# ProProject_Buck-Boost_1_2024-04-08.net
KiCad netlist of a schematic drawn in EasyEDA Pro
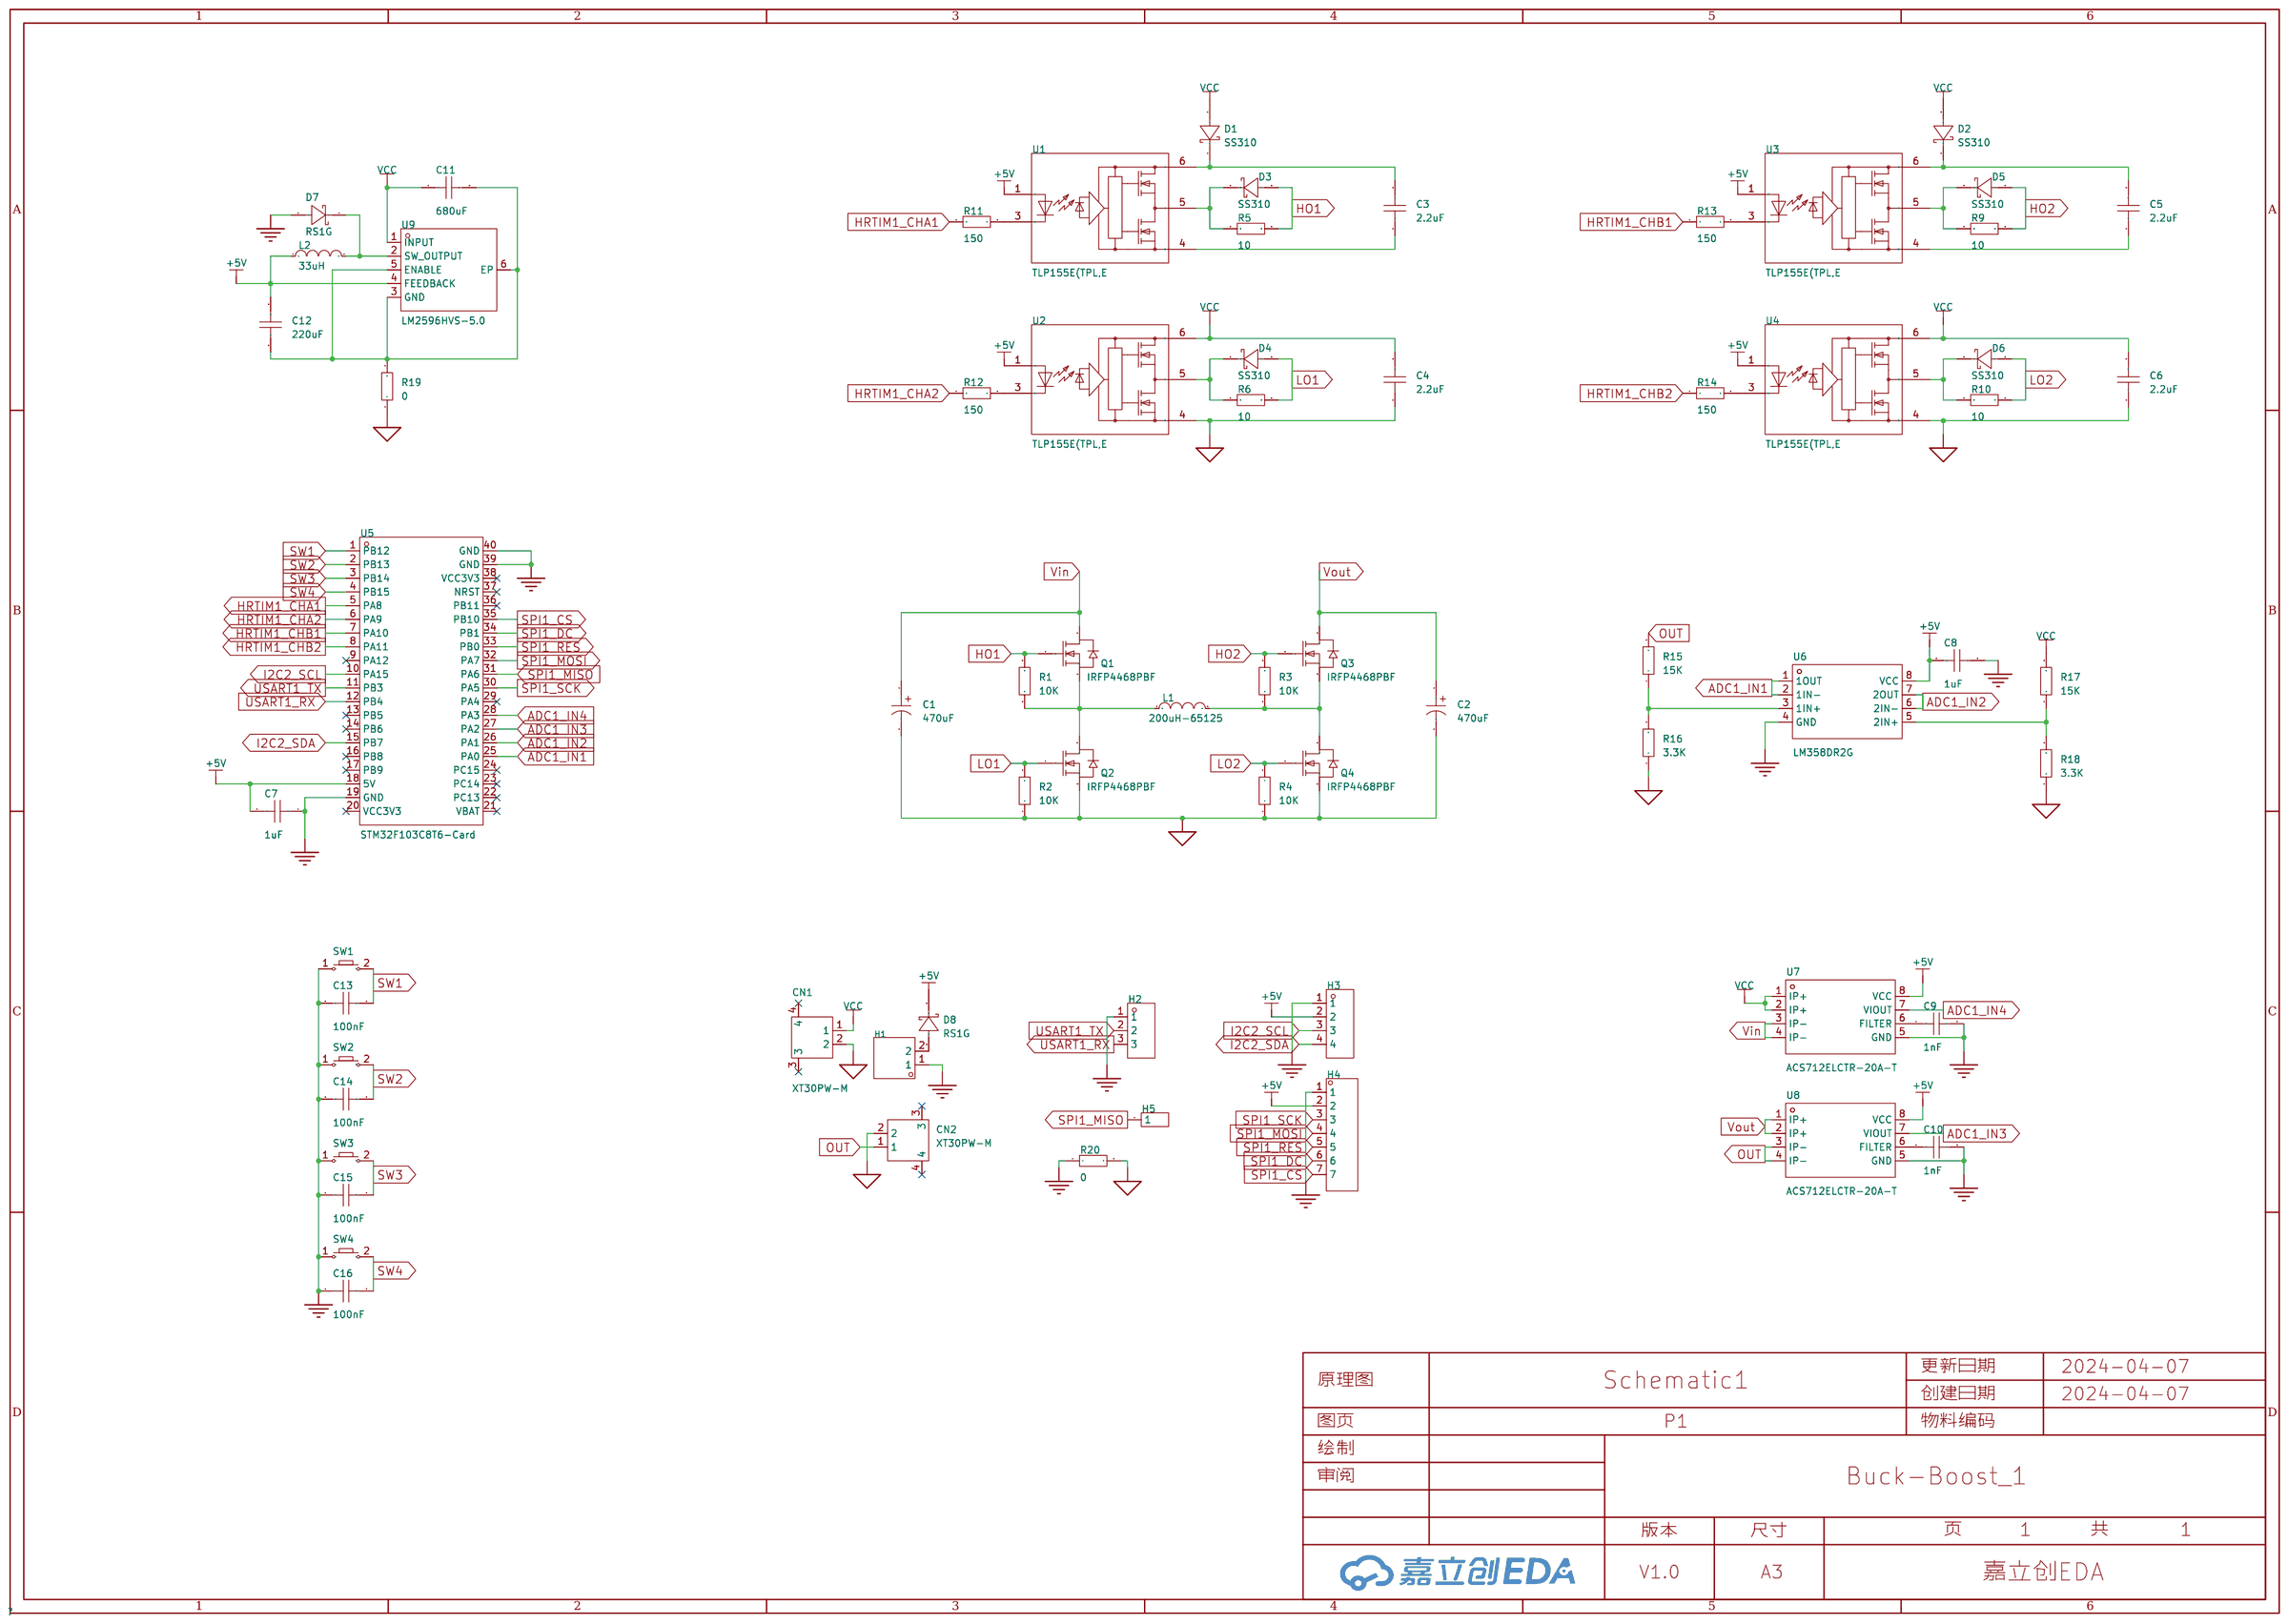
[diagram p0: schematic sheet]

(export (version "E")
  (design (tool "Eeschema 10.0.6"))
  (components
    (comp (ref "C1")
      (value "470uF")
      (footprint "easyedapro:CAP-TH_BD16.0-P7.50-D1.5-FD")
      (description "容值:470uF;精度:±20%;额定电压:120V;纹波电流:-;等效串联电阻:-;")
      (fields (field (name "Manufacturer Part") "ERS2BM471L35OT") (field (name "Manufacturer") "AISHI(艾华集团)"))
      (libsource (lib "easyedapro") (part "ERS2BM471L35OT"))
    )
    (comp (ref "C2")
      (value "470uF")
      (footprint "easyedapro:CAP-TH_BD16.0-P7.50-D1.5-FD")
      (description "容值:470uF;精度:±20%;额定电压:120V;纹波电流:-;等效串联电阻:-;")
      (fields (field (name "Manufacturer Part") "ERS2BM471L35OT") (field (name "Manufacturer") "AISHI(艾华集团)"))
      (libsource (lib "easyedapro") (part "ERS2BM471L35OT"))
    )
    (comp (ref "C3")
      (value "2.2uF")
      (footprint "easyedapro:C0603")
      (libsource (lib "easyedapro") (part "CapAcitance"))
    )
    (comp (ref "C4")
      (value "2.2uF")
      (footprint "easyedapro:C0603")
      (libsource (lib "easyedapro") (part "CapAcitance"))
    )
    (comp (ref "C5")
      (value "2.2uF")
      (footprint "easyedapro:C0603")
      (libsource (lib "easyedapro") (part "CapAcitance"))
    )
    (comp (ref "C6")
      (value "2.2uF")
      (footprint "easyedapro:C0603")
      (libsource (lib "easyedapro") (part "CapAcitance"))
    )
    (comp (ref "C7")
      (value "1uF")
      (footprint "easyedapro:C0603")
      (libsource (lib "easyedapro") (part "CapAcitance"))
    )
    (comp (ref "C8")
      (value "1uF")
      (footprint "easyedapro:C0603")
      (libsource (lib "easyedapro") (part "CapAcitance"))
    )
    (comp (ref "C9")
      (value "1nF")
      (footprint "easyedapro:C0603")
      (libsource (lib "easyedapro") (part "CapAcitance"))
    )
    (comp (ref "C10")
      (value "1nF")
      (footprint "easyedapro:C0603")
      (libsource (lib "easyedapro") (part "CapAcitance"))
    )
    (comp (ref "C11")
      (value "680uF")
      (footprint "easyedapro:C0603")
      (libsource (lib "easyedapro") (part "CapAcitance"))
    )
    (comp (ref "C12")
      (value "220uF")
      (footprint "easyedapro:C0603")
      (libsource (lib "easyedapro") (part "CapAcitance"))
    )
    (comp (ref "C13")
      (value "100nF")
      (footprint "easyedapro:C0603")
      (libsource (lib "easyedapro") (part "CapAcitance"))
    )
    (comp (ref "C14")
      (value "100nF")
      (footprint "easyedapro:C0603")
      (libsource (lib "easyedapro") (part "CapAcitance"))
    )
    (comp (ref "C15")
      (value "100nF")
      (footprint "easyedapro:C0603")
      (libsource (lib "easyedapro") (part "CapAcitance"))
    )
    (comp (ref "C16")
      (value "100nF")
      (footprint "easyedapro:C0603")
      (libsource (lib "easyedapro") (part "CapAcitance"))
    )
    (comp (ref "CN1")
      (value "XT30PW-M")
      (footprint "easyedapro:CONN-TH_XT30PW-M")
      (description "类别:-;类型1:-;")
      (fields (field (name "Manufacturer") "AMASS(艾迈斯)"))
      (libsource (lib "easyedapro") (part "XT30PW-M"))
    )
    (comp (ref "CN2")
      (value "XT30PW-M")
      (footprint "easyedapro:CONN-TH_XT30PW-M")
      (description "类别:-;类型1:-;")
      (fields (field (name "Manufacturer") "AMASS(艾迈斯)"))
      (libsource (lib "easyedapro") (part "XT30PW-M"))
    )
    (comp (ref "D1")
      (value "SS310")
      (footprint "easyedapro:SMC_L6.9-W5.9-LS7.9-RD")
      (fields (field (name "Manufacturer") "MDD"))
      (libsource (lib "easyedapro") (part "SS56_C5161914"))
    )
    (comp (ref "D2")
      (value "SS310")
      (footprint "easyedapro:SMC_L6.9-W5.9-LS7.9-RD")
      (fields (field (name "Manufacturer") "MDD"))
      (libsource (lib "easyedapro") (part "SS56_C5161914"))
    )
    (comp (ref "D3")
      (value "SS310")
      (footprint "easyedapro:SMC_L6.9-W5.9-LS7.9-RD")
      (fields (field (name "Manufacturer") "MDD"))
      (libsource (lib "easyedapro") (part "SS56_C5161914"))
    )
    (comp (ref "D4")
      (value "SS310")
      (footprint "easyedapro:SMC_L6.9-W5.9-LS7.9-RD")
      (fields (field (name "Manufacturer") "MDD"))
      (libsource (lib "easyedapro") (part "SS56_C5161914"))
    )
    (comp (ref "D5")
      (value "SS310")
      (footprint "easyedapro:SMC_L6.9-W5.9-LS7.9-RD")
      (fields (field (name "Manufacturer") "MDD"))
      (libsource (lib "easyedapro") (part "SS56_C5161914"))
    )
    (comp (ref "D6")
      (value "SS310")
      (footprint "easyedapro:SMC_L6.9-W5.9-LS7.9-RD")
      (fields (field (name "Manufacturer") "MDD"))
      (libsource (lib "easyedapro") (part "SS56_C5161914"))
    )
    (comp (ref "D7")
      (value "RS1G")
      (footprint "easyedapro:SMC_L6.9-W5.9-LS7.9-RD")
      (fields (field (name "Manufacturer") "宏迦橙"))
      (libsource (lib "easyedapro") (part "SS56_C5161914"))
    )
    (comp (ref "D8")
      (value "RS1G")
      (footprint "easyedapro:SMC_L6.9-W5.9-LS7.9-RD")
      (fields (field (name "Manufacturer") "宏迦橙"))
      (libsource (lib "easyedapro") (part "SS56_C5161914"))
    )
    (comp (ref "H1")
      (value "~")
      (footprint "easyedapro:HDR-TH_2P-P2.54-V-M-1")
      (libsource (lib "easyedapro") (part "210S-1*2P L=11.6MMGold-plated black"))
    )
    (comp (ref "H2")
      (value "~")
      (footprint "easyedapro:HDR-TH_3P-P2.54-V-M")
      (libsource (lib "easyedapro") (part "PZ254V-11-03P_C2937625"))
    )
    (comp (ref "H3")
      (value "~")
      (footprint "easyedapro:HDR-TH_4P-P2.54-V-F")
      (libsource (lib "easyedapro") (part "2.54-1*4P母"))
    )
    (comp (ref "H4")
      (value "~")
      (footprint "easyedapro:HDR-TH_7P-P2.54-V-F")
      (libsource (lib "easyedapro") (part "220S-1*7P H=8.5MM Ytype Gold-plated"))
    )
    (comp (ref "H5")
      (value "~")
      (footprint "easyedapro:HDR-TH_1P-V-M_XKB_X4611WV-01I-C28D40")
      (libsource (lib "easyedapro") (part "HDR_1x1"))
    )
    (comp (ref "L1")
      (value "200uH-65125")
      (footprint "easyedapro:IND-TH_200UH-65125")
      (libsource (lib "easyedapro") (part "200UH-65125"))
    )
    (comp (ref "L2")
      (value "33uH")
      (footprint "easyedapro:L0603")
      (fields
        (field (name "Manufacturer Part") "MGV0603330M-10")
        (field (name "Manufacturer") "Laird-Signal Integrity Products")
      )
      (libsource (lib "easyedapro") (part "SDFL1608S100KTF"))
    )
    (comp (ref "Q1")
      (value "IRFP4468PBF")
      (footprint "easyedapro:TO-247AC-3_L15.8-W5.0-P5.46-L")
      (fields (field (name "Manufacturer") "Infineon(英飞凌)"))
      (libsource (lib "easyedapro") (part "IRFP4468PBF"))
    )
    (comp (ref "Q2")
      (value "IRFP4468PBF")
      (footprint "easyedapro:TO-247AC-3_L15.8-W5.0-P5.46-L")
      (fields (field (name "Manufacturer") "Infineon(英飞凌)"))
      (libsource (lib "easyedapro") (part "IRFP4468PBF"))
    )
    (comp (ref "Q3")
      (value "IRFP4468PBF")
      (footprint "easyedapro:TO-247AC-3_L15.8-W5.0-P5.46-L")
      (fields (field (name "Manufacturer") "Infineon(英飞凌)"))
      (libsource (lib "easyedapro") (part "IRFP4468PBF"))
    )
    (comp (ref "Q4")
      (value "IRFP4468PBF")
      (footprint "easyedapro:TO-247AC-3_L15.8-W5.0-P5.46-L")
      (fields (field (name "Manufacturer") "Infineon(英飞凌)"))
      (libsource (lib "easyedapro") (part "IRFP4468PBF"))
    )
    (comp (ref "R1") (value "10K") (footprint "easyedapro:R0603") (libsource (lib "easyedapro") (part "电阻")))
    (comp (ref "R2") (value "10K") (footprint "easyedapro:R0603") (libsource (lib "easyedapro") (part "电阻")))
    (comp (ref "R3") (value "10K") (footprint "easyedapro:R0603") (libsource (lib "easyedapro") (part "电阻")))
    (comp (ref "R4") (value "10K") (footprint "easyedapro:R0603") (libsource (lib "easyedapro") (part "电阻")))
    (comp (ref "R5") (value "10") (footprint "easyedapro:R0603") (libsource (lib "easyedapro") (part "电阻")))
    (comp (ref "R6") (value "10") (footprint "easyedapro:R0603") (libsource (lib "easyedapro") (part "电阻")))
    (comp (ref "R9") (value "10") (footprint "easyedapro:R0603") (libsource (lib "easyedapro") (part "电阻")))
    (comp (ref "R10") (value "10") (footprint "easyedapro:R0603") (libsource (lib "easyedapro") (part "电阻")))
    (comp (ref "R11") (value "150") (footprint "easyedapro:R0603") (libsource (lib "easyedapro") (part "电阻")))
    (comp (ref "R12") (value "150") (footprint "easyedapro:R0603") (libsource (lib "easyedapro") (part "电阻")))
    (comp (ref "R13") (value "150") (footprint "easyedapro:R0603") (libsource (lib "easyedapro") (part "电阻")))
    (comp (ref "R14") (value "150") (footprint "easyedapro:R0603") (libsource (lib "easyedapro") (part "电阻")))
    (comp (ref "R15") (value "15K") (footprint "easyedapro:R0603") (libsource (lib "easyedapro") (part "电阻")))
    (comp (ref "R16")
      (value "3.3K")
      (footprint "easyedapro:R0603")
      (libsource (lib "easyedapro") (part "电阻"))
    )
    (comp (ref "R17") (value "15K") (footprint "easyedapro:R0603") (libsource (lib "easyedapro") (part "电阻")))
    (comp (ref "R18")
      (value "3.3K")
      (footprint "easyedapro:R0603")
      (libsource (lib "easyedapro") (part "电阻"))
    )
    (comp (ref "R19") (value "0") (footprint "easyedapro:R0603") (libsource (lib "easyedapro") (part "电阻")))
    (comp (ref "R20") (value "0") (footprint "easyedapro:R0603") (libsource (lib "easyedapro") (part "电阻")))
    (comp (ref "SW1")
      (value "~")
      (footprint "easyedapro:Key_SMD_3x4x2")
      (libsource (lib "easyedapro") (part "轻触按键x2"))
    )
    (comp (ref "SW2")
      (value "~")
      (footprint "easyedapro:Key_SMD_3x4x2")
      (libsource (lib "easyedapro") (part "轻触按键x2"))
    )
    (comp (ref "SW3")
      (value "~")
      (footprint "easyedapro:Key_SMD_3x4x2")
      (libsource (lib "easyedapro") (part "轻触按键x2"))
    )
    (comp (ref "SW4")
      (value "~")
      (footprint "easyedapro:Key_SMD_3x4x2")
      (libsource (lib "easyedapro") (part "轻触按键x2"))
    )
    (comp (ref "U1")
      (value "TLP155E(TPL,E")
      (footprint "easyedapro:OPTO-SMD-5_L3.7-W4.6-P1.27-LS7.0-BR")
      (description "输入类型:DC;电源电压:10V~30V;共模瞬变抗扰度CMTI:15kV/us;传播延迟tpLH/tpHL:170ns；170ns;")
      (fields (field (name "Manufacturer") "TOSHIBA(东芝)"))
      (libsource (lib "easyedapro") (part "TLP155E(TPL,E"))
    )
    (comp (ref "U2")
      (value "TLP155E(TPL,E")
      (footprint "easyedapro:OPTO-SMD-5_L3.7-W4.6-P1.27-LS7.0-BR")
      (description "输入类型:DC;电源电压:10V~30V;共模瞬变抗扰度CMTI:15kV/us;传播延迟tpLH/tpHL:170ns；170ns;")
      (fields (field (name "Manufacturer") "TOSHIBA(东芝)"))
      (libsource (lib "easyedapro") (part "TLP155E(TPL,E"))
    )
    (comp (ref "U3")
      (value "TLP155E(TPL,E")
      (footprint "easyedapro:OPTO-SMD-5_L3.7-W4.6-P1.27-LS7.0-BR")
      (description "输入类型:DC;电源电压:10V~30V;共模瞬变抗扰度CMTI:15kV/us;传播延迟tpLH/tpHL:170ns；170ns;")
      (fields (field (name "Manufacturer") "TOSHIBA(东芝)"))
      (libsource (lib "easyedapro") (part "TLP155E(TPL,E"))
    )
    (comp (ref "U4")
      (value "TLP155E(TPL,E")
      (footprint "easyedapro:OPTO-SMD-5_L3.7-W4.6-P1.27-LS7.0-BR")
      (description "输入类型:DC;电源电压:10V~30V;共模瞬变抗扰度CMTI:15kV/us;传播延迟tpLH/tpHL:170ns；170ns;")
      (fields (field (name "Manufacturer") "TOSHIBA(东芝)"))
      (libsource (lib "easyedapro") (part "TLP155E(TPL,E"))
    )
    (comp (ref "U5")
      (value "STM32F103C8T6-Card")
      (footprint "easyedapro:CONN-TH_L53.3-W22.9_STM32F103C8T6-CARD")
      (libsource (lib "easyedapro") (part "STM32F103C8T6-CARD"))
    )
    (comp (ref "U6")
      (value "LM358DR2G")
      (footprint "easyedapro:SOIC-8_L5.0-W4.0-P1.27-LS6.0-BL")
      (description "放大器数:双路;增益带宽积(GBP):1MHz;输入偏置电流(Ib):45nA;压摆率(SR):-;带宽(-3db):-;")
      (fields (field (name "Manufacturer") "onsemi(安森美)"))
      (libsource (lib "easyedapro") (part "LM358DR2G"))
    )
    (comp (ref "U7")
      (value "ACS712ELCTR-20A-T")
      (footprint "easyedapro:SOIC-8_L4.9-W3.9-P1.27-LS6.0-BL")
      (description "电流测量范围:20A;灵敏度:100mV/A;")
      (fields (field (name "Manufacturer") "ALLEGRO(美国埃戈罗)"))
      (libsource (lib "easyedapro") (part "ACS712ELCTR-20A-T"))
    )
    (comp (ref "U8")
      (value "ACS712ELCTR-20A-T")
      (footprint "easyedapro:SOIC-8_L4.9-W3.9-P1.27-LS6.0-BL")
      (description "电流测量范围:20A;灵敏度:100mV/A;")
      (fields (field (name "Manufacturer") "ALLEGRO(美国埃戈罗)"))
      (libsource (lib "easyedapro") (part "ACS712ELCTR-20A-T"))
    )
    (comp (ref "U9")
      (value "LM2596HVS-5.0")
      (footprint "easyedapro:TO-263-5_L10.0-W9.0-P1.70-LS15.0-BL")
      (fields (field (name "Manufacturer") "TECH PUBLIC(台舟)"))
      (libsource (lib "easyedapro") (part "LM2596HVS-5.0_C18197847"))
    )
  )
  (nets
    (net (code "1") (name "+5V") (class "Default")
      (node (ref "C12") (pin "2") (pinfunction "2_2") (pintype "input"))
      (node (ref "C7") (pin "2") (pinfunction "2_2") (pintype "input"))
      (node (ref "C8") (pin "1") (pinfunction "1_1") (pintype "input"))
      (node (ref "D8") (pin "1") (pinfunction "K_1") (pintype "unspecified"))
      (node (ref "H3") (pin "2") (pinfunction "2_2") (pintype "unspecified"))
      (node (ref "H4") (pin "2") (pinfunction "2_2") (pintype "unspecified"))
      (node (ref "L2") (pin "1") (pinfunction "1_1") (pintype "unspecified"))
      (node (ref "U1") (pin "1") (pinfunction "AN_1") (pintype "unspecified"))
      (node (ref "U2") (pin "1") (pinfunction "AN_1") (pintype "unspecified"))
      (node (ref "U3") (pin "1") (pinfunction "AN_1") (pintype "unspecified"))
      (node (ref "U4") (pin "1") (pinfunction "AN_1") (pintype "unspecified"))
      (node (ref "U5") (pin "18") (pinfunction "5V_18") (pintype "unspecified"))
      (node (ref "U6") (pin "8") (pinfunction "VCC_8") (pintype "unspecified"))
      (node (ref "U7") (pin "8") (pinfunction "VCC_8") (pintype "unspecified"))
      (node (ref "U8") (pin "8") (pinfunction "VCC_8") (pintype "unspecified"))
      (node (ref "U9") (pin "4") (pinfunction "FEEDBACK_4") (pintype "unspecified"))
    )
    (net (code "2") (name "ADC1_IN1") (class "Default")
      (node (ref "U5") (pin "25") (pinfunction "PA0_25") (pintype "unspecified"))
      (node (ref "U6") (pin "1") (pinfunction "1OUT_1") (pintype "unspecified"))
      (node (ref "U6") (pin "2") (pinfunction "1IN-_2") (pintype "unspecified"))
    )
    (net (code "3") (name "ADC1_IN2") (class "Default")
      (node (ref "U5") (pin "26") (pinfunction "PA1_26") (pintype "unspecified"))
      (node (ref "U6") (pin "6") (pinfunction "2IN-_6") (pintype "unspecified"))
      (node (ref "U6") (pin "7") (pinfunction "2OUT_7") (pintype "unspecified"))
    )
    (net (code "4") (name "ADC1_IN3") (class "Default")
      (node (ref "U5") (pin "27") (pinfunction "PA2_27") (pintype "unspecified"))
      (node (ref "U8") (pin "7") (pinfunction "VIOUT_7") (pintype "unspecified"))
    )
    (net (code "5") (name "ADC1_IN4") (class "Default")
      (node (ref "U5") (pin "28") (pinfunction "PA3_28") (pintype "unspecified"))
      (node (ref "U7") (pin "7") (pinfunction "VIOUT_7") (pintype "unspecified"))
    )
    (net (code "6") (name "AGND") (class "Default")
      (node (ref "C1") (pin "2") (pinfunction "2_2") (pintype "input"))
      (node (ref "C2") (pin "2") (pinfunction "2_2") (pintype "input"))
      (node (ref "C4") (pin "1") (pinfunction "1_1") (pintype "input"))
      (node (ref "C6") (pin "1") (pinfunction "1_1") (pintype "input"))
      (node (ref "CN1") (pin "2") (pinfunction "2_2") (pintype "unspecified"))
      (node (ref "CN2") (pin "2") (pinfunction "2_2") (pintype "unspecified"))
      (node (ref "Q2") (pin "3") (pinfunction "S_3") (pintype "unspecified"))
      (node (ref "Q4") (pin "3") (pinfunction "S_3") (pintype "unspecified"))
      (node (ref "R16") (pin "1") (pinfunction "1_1") (pintype "input"))
      (node (ref "R18") (pin "1") (pinfunction "1_1") (pintype "input"))
      (node (ref "R19") (pin "1") (pinfunction "1_1") (pintype "input"))
      (node (ref "R2") (pin "1") (pinfunction "1_1") (pintype "input"))
      (node (ref "R20") (pin "2") (pinfunction "2_2") (pintype "input"))
      (node (ref "R4") (pin "1") (pinfunction "1_1") (pintype "input"))
      (node (ref "U2") (pin "4") (pinfunction "GND_4") (pintype "unspecified"))
      (node (ref "U4") (pin "4") (pinfunction "GND_4") (pintype "unspecified"))
    )
    (net (code "7") (name "GND") (class "Default")
      (node (ref "C10") (pin "2") (pinfunction "2_2") (pintype "input"))
      (node (ref "C13") (pin "1") (pinfunction "1_1") (pintype "input"))
      (node (ref "C14") (pin "1") (pinfunction "1_1") (pintype "input"))
      (node (ref "C15") (pin "1") (pinfunction "1_1") (pintype "input"))
      (node (ref "C16") (pin "1") (pinfunction "1_1") (pintype "input"))
      (node (ref "C7") (pin "1") (pinfunction "1_1") (pintype "input"))
      (node (ref "C8") (pin "2") (pinfunction "2_2") (pintype "input"))
      (node (ref "C9") (pin "2") (pinfunction "2_2") (pintype "input"))
      (node (ref "D7") (pin "2") (pinfunction "A_2") (pintype "unspecified"))
      (node (ref "H1") (pin "1") (pinfunction "1_1") (pintype "input"))
      (node (ref "H2") (pin "1") (pinfunction "1_1") (pintype "input"))
      (node (ref "H3") (pin "1") (pinfunction "1_1") (pintype "unspecified"))
      (node (ref "H4") (pin "1") (pinfunction "1_1") (pintype "unspecified"))
      (node (ref "R20") (pin "1") (pinfunction "1_1") (pintype "input"))
      (node (ref "SW1") (pin "1") (pinfunction "1_1") (pintype "input"))
      (node (ref "SW2") (pin "1") (pinfunction "1_1") (pintype "input"))
      (node (ref "SW3") (pin "1") (pinfunction "1_1") (pintype "input"))
      (node (ref "SW4") (pin "1") (pinfunction "1_1") (pintype "input"))
      (node (ref "U5") (pin "19") (pinfunction "GND_19") (pintype "unspecified"))
      (node (ref "U5") (pin "39") (pinfunction "GND_39") (pintype "unspecified"))
      (node (ref "U5") (pin "40") (pinfunction "GND_40") (pintype "unspecified"))
      (node (ref "U6") (pin "4") (pinfunction "GND_4") (pintype "unspecified"))
      (node (ref "U7") (pin "5") (pinfunction "GND_5") (pintype "unspecified"))
      (node (ref "U8") (pin "5") (pinfunction "GND_5") (pintype "unspecified"))
    )
    (net (code "8") (name "HO1") (class "Default")
      (node (ref "D3") (pin "2") (pinfunction "A_2") (pintype "unspecified"))
      (node (ref "Q1") (pin "1") (pinfunction "G_1") (pintype "unspecified"))
      (node (ref "R1") (pin "2") (pinfunction "2_2") (pintype "input"))
      (node (ref "R5") (pin "2") (pinfunction "2_2") (pintype "input"))
    )
    (net (code "9") (name "HO2") (class "Default")
      (node (ref "D5") (pin "2") (pinfunction "A_2") (pintype "unspecified"))
      (node (ref "Q3") (pin "1") (pinfunction "G_1") (pintype "unspecified"))
      (node (ref "R3") (pin "2") (pinfunction "2_2") (pintype "input"))
      (node (ref "R9") (pin "2") (pinfunction "2_2") (pintype "input"))
    )
    (net (code "10") (name "HRTIM1_CHA1") (class "Default")
      (node (ref "R11") (pin "1") (pinfunction "1_1") (pintype "input"))
      (node (ref "U5") (pin "5") (pinfunction "PA8_5") (pintype "unspecified"))
    )
    (net (code "11") (name "HRTIM1_CHA2") (class "Default")
      (node (ref "R12") (pin "1") (pinfunction "1_1") (pintype "input"))
      (node (ref "U5") (pin "6") (pinfunction "PA9_6") (pintype "unspecified"))
    )
    (net (code "12") (name "HRTIM1_CHB1") (class "Default")
      (node (ref "R13") (pin "1") (pinfunction "1_1") (pintype "input"))
      (node (ref "U5") (pin "7") (pinfunction "PA10_7") (pintype "unspecified"))
    )
    (net (code "13") (name "HRTIM1_CHB2") (class "Default")
      (node (ref "R14") (pin "1") (pinfunction "1_1") (pintype "input"))
      (node (ref "U5") (pin "8") (pinfunction "PA11_8") (pintype "unspecified"))
    )
    (net (code "14") (name "I2C2_SCL") (class "Default")
      (node (ref "H3") (pin "3") (pinfunction "3_3") (pintype "unspecified"))
      (node (ref "U5") (pin "10") (pinfunction "PA15_10") (pintype "unspecified"))
    )
    (net (code "15") (name "I2C2_SDA") (class "Default")
      (node (ref "H3") (pin "4") (pinfunction "4_4") (pintype "unspecified"))
      (node (ref "U5") (pin "15") (pinfunction "PB7_15") (pintype "unspecified"))
    )
    (net (code "16") (name "LO1") (class "Default")
      (node (ref "D4") (pin "2") (pinfunction "A_2") (pintype "unspecified"))
      (node (ref "Q2") (pin "1") (pinfunction "G_1") (pintype "unspecified"))
      (node (ref "R2") (pin "2") (pinfunction "2_2") (pintype "input"))
      (node (ref "R6") (pin "2") (pinfunction "2_2") (pintype "input"))
    )
    (net (code "17") (name "LO2") (class "Default")
      (node (ref "D6") (pin "2") (pinfunction "A_2") (pintype "unspecified"))
      (node (ref "Q4") (pin "1") (pinfunction "G_1") (pintype "unspecified"))
      (node (ref "R10") (pin "2") (pinfunction "2_2") (pintype "input"))
      (node (ref "R4") (pin "2") (pinfunction "2_2") (pintype "input"))
    )
    (net (code "18") (name "Net-(D1-K)") (class "Default")
      (node (ref "C3") (pin "2") (pinfunction "2_2") (pintype "input"))
      (node (ref "D1") (pin "1") (pinfunction "K_1") (pintype "unspecified"))
      (node (ref "U1") (pin "6") (pinfunction "VCC_6") (pintype "unspecified"))
    )
    (net (code "19") (name "Net-(D2-K)") (class "Default")
      (node (ref "C5") (pin "2") (pinfunction "2_2") (pintype "input"))
      (node (ref "D2") (pin "1") (pinfunction "K_1") (pintype "unspecified"))
      (node (ref "U3") (pin "6") (pinfunction "VCC_6") (pintype "unspecified"))
    )
    (net (code "20") (name "Net-(D3-K)") (class "Default")
      (node (ref "D3") (pin "1") (pinfunction "K_1") (pintype "unspecified"))
      (node (ref "R5") (pin "1") (pinfunction "1_1") (pintype "input"))
      (node (ref "U1") (pin "5") (pinfunction "VO_5") (pintype "unspecified"))
    )
    (net (code "21") (name "Net-(D4-K)") (class "Default")
      (node (ref "D4") (pin "1") (pinfunction "K_1") (pintype "unspecified"))
      (node (ref "R6") (pin "1") (pinfunction "1_1") (pintype "input"))
      (node (ref "U2") (pin "5") (pinfunction "VO_5") (pintype "unspecified"))
    )
    (net (code "22") (name "Net-(D5-K)") (class "Default")
      (node (ref "D5") (pin "1") (pinfunction "K_1") (pintype "unspecified"))
      (node (ref "R9") (pin "1") (pinfunction "1_1") (pintype "input"))
      (node (ref "U3") (pin "5") (pinfunction "VO_5") (pintype "unspecified"))
    )
    (net (code "23") (name "Net-(D6-K)") (class "Default")
      (node (ref "D6") (pin "1") (pinfunction "K_1") (pintype "unspecified"))
      (node (ref "R10") (pin "1") (pinfunction "1_1") (pintype "input"))
      (node (ref "U4") (pin "5") (pinfunction "VO_5") (pintype "unspecified"))
    )
    (net (code "24") (name "Net-(D7-K)") (class "Default")
      (node (ref "D7") (pin "1") (pinfunction "K_1") (pintype "unspecified"))
      (node (ref "L2") (pin "2") (pinfunction "2_2") (pintype "unspecified"))
      (node (ref "U9") (pin "2") (pinfunction "SW_OUTPUT_2") (pintype "unspecified"))
    )
    (net (code "25") (name "Net-(D8-A)") (class "Default")
      (node (ref "D8") (pin "2") (pinfunction "A_2") (pintype "unspecified"))
      (node (ref "H1") (pin "2") (pinfunction "2_2") (pintype "input"))
    )
    (net (code "26") (name "Net-(Q1-S)") (class "Default")
      (node (ref "L1") (pin "1") (pinfunction "1_1") (pintype "input"))
      (node (ref "Q1") (pin "3") (pinfunction "S_3") (pintype "unspecified"))
      (node (ref "Q2") (pin "2") (pinfunction "D_2") (pintype "unspecified"))
      (node (ref "R1") (pin "1") (pinfunction "1_1") (pintype "input"))
    )
    (net (code "27") (name "Net-(Q3-S)") (class "Default")
      (node (ref "L1") (pin "2") (pinfunction "2_2") (pintype "input"))
      (node (ref "Q3") (pin "3") (pinfunction "S_3") (pintype "unspecified"))
      (node (ref "Q4") (pin "2") (pinfunction "D_2") (pintype "unspecified"))
      (node (ref "R3") (pin "1") (pinfunction "1_1") (pintype "input"))
    )
    (net (code "28") (name "Net-(U1-CAT)") (class "Default")
      (node (ref "R11") (pin "2") (pinfunction "2_2") (pintype "input"))
      (node (ref "U1") (pin "3") (pinfunction "CAT_3") (pintype "unspecified"))
    )
    (net (code "29") (name "Net-(U1-GND)") (class "Default")
      (node (ref "C3") (pin "1") (pinfunction "1_1") (pintype "input"))
      (node (ref "U1") (pin "4") (pinfunction "GND_4") (pintype "unspecified"))
    )
    (net (code "30") (name "Net-(U2-CAT)") (class "Default")
      (node (ref "R12") (pin "2") (pinfunction "2_2") (pintype "input"))
      (node (ref "U2") (pin "3") (pinfunction "CAT_3") (pintype "unspecified"))
    )
    (net (code "31") (name "Net-(U3-CAT)") (class "Default")
      (node (ref "R13") (pin "2") (pinfunction "2_2") (pintype "input"))
      (node (ref "U3") (pin "3") (pinfunction "CAT_3") (pintype "unspecified"))
    )
    (net (code "32") (name "Net-(U3-GND)") (class "Default")
      (node (ref "C5") (pin "1") (pinfunction "1_1") (pintype "input"))
      (node (ref "U3") (pin "4") (pinfunction "GND_4") (pintype "unspecified"))
    )
    (net (code "33") (name "Net-(U4-CAT)") (class "Default")
      (node (ref "R14") (pin "2") (pinfunction "2_2") (pintype "input"))
      (node (ref "U4") (pin "3") (pinfunction "CAT_3") (pintype "unspecified"))
    )
    (net (code "34") (name "Net-(U6-1IN+)") (class "Default")
      (node (ref "R15") (pin "1") (pinfunction "1_1") (pintype "input"))
      (node (ref "R16") (pin "2") (pinfunction "2_2") (pintype "input"))
      (node (ref "U6") (pin "3") (pinfunction "1IN+_3") (pintype "unspecified"))
    )
    (net (code "35") (name "Net-(U6-2IN+)") (class "Default")
      (node (ref "R17") (pin "1") (pinfunction "1_1") (pintype "input"))
      (node (ref "R18") (pin "2") (pinfunction "2_2") (pintype "input"))
      (node (ref "U6") (pin "5") (pinfunction "2IN+_5") (pintype "unspecified"))
    )
    (net (code "36") (name "Net-(U7-FILTER)") (class "Default")
      (node (ref "C9") (pin "1") (pinfunction "1_1") (pintype "input"))
      (node (ref "U7") (pin "6") (pinfunction "FILTER_6") (pintype "unspecified"))
    )
    (net (code "37") (name "Net-(U8-FILTER)") (class "Default")
      (node (ref "C10") (pin "1") (pinfunction "1_1") (pintype "input"))
      (node (ref "U8") (pin "6") (pinfunction "FILTER_6") (pintype "unspecified"))
    )
    (net (code "38") (name "Net-(U9-ENABLE)") (class "Default")
      (node (ref "C11") (pin "2") (pinfunction "2_2") (pintype "input"))
      (node (ref "C12") (pin "1") (pinfunction "1_1") (pintype "input"))
      (node (ref "R19") (pin "2") (pinfunction "2_2") (pintype "input"))
      (node (ref "U9") (pin "3") (pinfunction "GND_3") (pintype "unspecified"))
      (node (ref "U9") (pin "5") (pinfunction "ENABLE_5") (pintype "unspecified"))
      (node (ref "U9") (pin "6") (pinfunction "EP_6") (pintype "unspecified"))
    )
    (net (code "39") (name "OUT") (class "Default")
      (node (ref "CN2") (pin "1") (pinfunction "1_1") (pintype "unspecified"))
      (node (ref "R15") (pin "2") (pinfunction "2_2") (pintype "input"))
      (node (ref "U8") (pin "3") (pinfunction "IP-_3") (pintype "unspecified"))
      (node (ref "U8") (pin "4") (pinfunction "IP-_4") (pintype "unspecified"))
    )
    (net (code "40") (name "SPI1_CS") (class "Default")
      (node (ref "H4") (pin "7") (pinfunction "7_7") (pintype "unspecified"))
      (node (ref "U5") (pin "35") (pinfunction "PB10_35") (pintype "unspecified"))
    )
    (net (code "41") (name "SPI1_DC") (class "Default")
      (node (ref "H4") (pin "6") (pinfunction "6_6") (pintype "unspecified"))
      (node (ref "U5") (pin "34") (pinfunction "PB1_34") (pintype "unspecified"))
    )
    (net (code "42") (name "SPI1_MISO") (class "Default")
      (node (ref "H5") (pin "1") (pinfunction "1_1") (pintype "unspecified"))
      (node (ref "U5") (pin "31") (pinfunction "PA6_31") (pintype "unspecified"))
    )
    (net (code "43") (name "SPI1_MOSI") (class "Default")
      (node (ref "H4") (pin "4") (pinfunction "4_4") (pintype "unspecified"))
      (node (ref "U5") (pin "32") (pinfunction "PA7_32") (pintype "unspecified"))
    )
    (net (code "44") (name "SPI1_RES") (class "Default")
      (node (ref "H4") (pin "5") (pinfunction "5_5") (pintype "unspecified"))
      (node (ref "U5") (pin "33") (pinfunction "PB0_33") (pintype "unspecified"))
    )
    (net (code "45") (name "SPI1_SCK") (class "Default")
      (node (ref "H4") (pin "3") (pinfunction "3_3") (pintype "unspecified"))
      (node (ref "U5") (pin "30") (pinfunction "PA5_30") (pintype "unspecified"))
    )
    (net (code "46") (name "SW1") (class "Default")
      (node (ref "C13") (pin "2") (pinfunction "2_2") (pintype "input"))
      (node (ref "SW1") (pin "2") (pinfunction "2_2") (pintype "input"))
      (node (ref "U5") (pin "1") (pinfunction "PB12_1") (pintype "unspecified"))
    )
    (net (code "47") (name "SW2") (class "Default")
      (node (ref "C14") (pin "2") (pinfunction "2_2") (pintype "input"))
      (node (ref "SW2") (pin "2") (pinfunction "2_2") (pintype "input"))
      (node (ref "U5") (pin "2") (pinfunction "PB13_2") (pintype "unspecified"))
    )
    (net (code "48") (name "SW3") (class "Default")
      (node (ref "C15") (pin "2") (pinfunction "2_2") (pintype "input"))
      (node (ref "SW3") (pin "2") (pinfunction "2_2") (pintype "input"))
      (node (ref "U5") (pin "3") (pinfunction "PB14_3") (pintype "unspecified"))
    )
    (net (code "49") (name "SW4") (class "Default")
      (node (ref "C16") (pin "2") (pinfunction "2_2") (pintype "input"))
      (node (ref "SW4") (pin "2") (pinfunction "2_2") (pintype "input"))
      (node (ref "U5") (pin "4") (pinfunction "PB15_4") (pintype "unspecified"))
    )
    (net (code "50") (name "USART1_RX") (class "Default")
      (node (ref "H2") (pin "3") (pinfunction "3_3") (pintype "input"))
      (node (ref "U5") (pin "12") (pinfunction "PB4_12") (pintype "unspecified"))
    )
    (net (code "51") (name "USART1_TX") (class "Default")
      (node (ref "H2") (pin "2") (pinfunction "2_2") (pintype "input"))
      (node (ref "U5") (pin "11") (pinfunction "PB3_11") (pintype "unspecified"))
    )
    (net (code "52") (name "VCC") (class "Default")
      (node (ref "C11") (pin "1") (pinfunction "1_1") (pintype "input"))
      (node (ref "C4") (pin "2") (pinfunction "2_2") (pintype "input"))
      (node (ref "C6") (pin "2") (pinfunction "2_2") (pintype "input"))
      (node (ref "CN1") (pin "1") (pinfunction "1_1") (pintype "unspecified"))
      (node (ref "D1") (pin "2") (pinfunction "A_2") (pintype "unspecified"))
      (node (ref "D2") (pin "2") (pinfunction "A_2") (pintype "unspecified"))
      (node (ref "R17") (pin "2") (pinfunction "2_2") (pintype "input"))
      (node (ref "U2") (pin "6") (pinfunction "VCC_6") (pintype "unspecified"))
      (node (ref "U4") (pin "6") (pinfunction "VCC_6") (pintype "unspecified"))
      (node (ref "U7") (pin "1") (pinfunction "IP+_1") (pintype "unspecified"))
      (node (ref "U7") (pin "2") (pinfunction "IP+_2") (pintype "unspecified"))
      (node (ref "U9") (pin "1") (pinfunction "INPUT_1") (pintype "unspecified"))
    )
    (net (code "53") (name "Vin") (class "Default")
      (node (ref "C1") (pin "1") (pinfunction "1_1") (pintype "input"))
      (node (ref "Q1") (pin "2") (pinfunction "D_2") (pintype "unspecified"))
      (node (ref "U7") (pin "3") (pinfunction "IP-_3") (pintype "unspecified"))
      (node (ref "U7") (pin "4") (pinfunction "IP-_4") (pintype "unspecified"))
    )
    (net (code "54") (name "Vout") (class "Default")
      (node (ref "C2") (pin "1") (pinfunction "1_1") (pintype "input"))
      (node (ref "Q3") (pin "2") (pinfunction "D_2") (pintype "unspecified"))
      (node (ref "U8") (pin "1") (pinfunction "IP+_1") (pintype "unspecified"))
      (node (ref "U8") (pin "2") (pinfunction "IP+_2") (pintype "unspecified"))
    )
    (net (code "55") (name "unconnected-(CN1-Pad3)") (class "Default")
      (node (ref "CN1") (pin "3") (pinfunction "3_3") (pintype "unspecified+no_connect"))
    )
    (net (code "56") (name "unconnected-(CN1-Pad4)") (class "Default")
      (node (ref "CN1") (pin "4") (pinfunction "4_4") (pintype "unspecified+no_connect"))
    )
    (net (code "57") (name "unconnected-(CN2-Pad3)") (class "Default")
      (node (ref "CN2") (pin "3") (pinfunction "3_3") (pintype "unspecified+no_connect"))
    )
    (net (code "58") (name "unconnected-(CN2-Pad4)") (class "Default")
      (node (ref "CN2") (pin "4") (pinfunction "4_4") (pintype "unspecified+no_connect"))
    )
    (net (code "59") (name "unconnected-(U5-NRST-Pad37)") (class "Default")
      (node (ref "U5") (pin "37") (pinfunction "NRST_37") (pintype "unspecified+no_connect"))
    )
    (net (code "60") (name "unconnected-(U5-PA4-Pad29)") (class "Default")
      (node (ref "U5") (pin "29") (pinfunction "PA4_29") (pintype "unspecified+no_connect"))
    )
    (net (code "61") (name "unconnected-(U5-PA12-Pad9)") (class "Default")
      (node (ref "U5") (pin "9") (pinfunction "PA12_9") (pintype "unspecified+no_connect"))
    )
    (net (code "62") (name "unconnected-(U5-PB5-Pad13)") (class "Default")
      (node (ref "U5") (pin "13") (pinfunction "PB5_13") (pintype "unspecified+no_connect"))
    )
    (net (code "63") (name "unconnected-(U5-PB6-Pad14)") (class "Default")
      (node (ref "U5") (pin "14") (pinfunction "PB6_14") (pintype "unspecified+no_connect"))
    )
    (net (code "64") (name "unconnected-(U5-PB8-Pad16)") (class "Default")
      (node (ref "U5") (pin "16") (pinfunction "PB8_16") (pintype "unspecified+no_connect"))
    )
    (net (code "65") (name "unconnected-(U5-PB9-Pad17)") (class "Default")
      (node (ref "U5") (pin "17") (pinfunction "PB9_17") (pintype "unspecified+no_connect"))
    )
    (net (code "66") (name "unconnected-(U5-PB11-Pad36)") (class "Default")
      (node (ref "U5") (pin "36") (pinfunction "PB11_36") (pintype "unspecified+no_connect"))
    )
    (net (code "67") (name "unconnected-(U5-PC13-Pad22)") (class "Default")
      (node (ref "U5") (pin "22") (pinfunction "PC13_22") (pintype "unspecified+no_connect"))
    )
    (net (code "68") (name "unconnected-(U5-PC14-Pad23)") (class "Default")
      (node (ref "U5") (pin "23") (pinfunction "PC14_23") (pintype "unspecified+no_connect"))
    )
    (net (code "69") (name "unconnected-(U5-PC15-Pad24)") (class "Default")
      (node (ref "U5") (pin "24") (pinfunction "PC15_24") (pintype "unspecified+no_connect"))
    )
    (net (code "70") (name "unconnected-(U5-VBAT-Pad21)") (class "Default")
      (node (ref "U5") (pin "21") (pinfunction "VBAT_21") (pintype "unspecified+no_connect"))
    )
    (net (code "71") (name "unconnected-(U5-VCC3V3-Pad20)") (class "Default")
      (node (ref "U5") (pin "20") (pinfunction "VCC3V3_20") (pintype "unspecified+no_connect"))
    )
    (net (code "72") (name "unconnected-(U5-VCC3V3-Pad38)") (class "Default")
      (node (ref "U5") (pin "38") (pinfunction "VCC3V3_38") (pintype "unspecified+no_connect"))
    )
  )
)
